# board.net
KiCad netlist of a schematic drawn in EAGLE
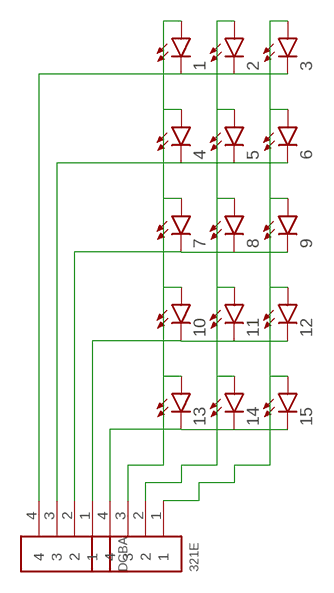
[diagram p0: schematic, sheet 1]

(export (version "E")
  (design (tool "Eeschema 10.0.6"))
  (components
    (comp (ref "1")
      (value "LED3MM")
      (footprint "eagle-import:LED3MM")
      (libsource (lib "eagle-import") (part "LED3MM"))
    )
    (comp (ref "2")
      (value "LED3MM")
      (footprint "eagle-import:LED3MM")
      (libsource (lib "eagle-import") (part "LED3MM"))
    )
    (comp (ref "3")
      (value "LED3MM")
      (footprint "eagle-import:LED3MM")
      (libsource (lib "eagle-import") (part "LED3MM"))
    )
    (comp (ref "4")
      (value "LED3MM")
      (footprint "eagle-import:LED3MM")
      (libsource (lib "eagle-import") (part "LED3MM"))
    )
    (comp (ref "5")
      (value "LED3MM")
      (footprint "eagle-import:LED3MM")
      (libsource (lib "eagle-import") (part "LED3MM"))
    )
    (comp (ref "6")
      (value "LED3MM")
      (footprint "eagle-import:LED3MM")
      (libsource (lib "eagle-import") (part "LED3MM"))
    )
    (comp (ref "7")
      (value "LED3MM")
      (footprint "eagle-import:LED3MM")
      (libsource (lib "eagle-import") (part "LED3MM"))
    )
    (comp (ref "8")
      (value "LED3MM")
      (footprint "eagle-import:LED3MM")
      (libsource (lib "eagle-import") (part "LED3MM"))
    )
    (comp (ref "9")
      (value "LED3MM")
      (footprint "eagle-import:LED3MM")
      (libsource (lib "eagle-import") (part "LED3MM"))
    )
    (comp (ref "10")
      (value "LED3MM")
      (footprint "eagle-import:LED3MM")
      (libsource (lib "eagle-import") (part "LED3MM"))
    )
    (comp (ref "11")
      (value "LED3MM")
      (footprint "eagle-import:LED3MM")
      (libsource (lib "eagle-import") (part "LED3MM"))
    )
    (comp (ref "12")
      (value "LED3MM")
      (footprint "eagle-import:LED3MM")
      (libsource (lib "eagle-import") (part "LED3MM"))
    )
    (comp (ref "13")
      (value "LED3MM")
      (footprint "eagle-import:LED3MM")
      (libsource (lib "eagle-import") (part "LED3MM"))
    )
    (comp (ref "14")
      (value "LED3MM")
      (footprint "eagle-import:LED3MM")
      (libsource (lib "eagle-import") (part "LED3MM"))
    )
    (comp (ref "15")
      (value "LED3MM")
      (footprint "eagle-import:LED3MM")
      (libsource (lib "eagle-import") (part "LED3MM"))
    )
    (comp (ref "321E")
      (value "1X4-BIG")
      (footprint "eagle-import:1X04-BIG")
      (libsource (lib "eagle-import") (part "1X4-BIG"))
    )
    (comp (ref "DCBA")
      (value "1X4-BIG")
      (footprint "eagle-import:1X04-BIG")
      (libsource (lib "eagle-import") (part "1X4-BIG"))
    )
  )
  (nets
    (net (code "1") (name "Net-(1-C)") (class "Default")
      (node (ref "1") (pin "K") (pinfunction "C_K") (pintype "passive"))
      (node (ref "2") (pin "K") (pinfunction "C_K") (pintype "passive"))
      (node (ref "3") (pin "K") (pinfunction "C_K") (pintype "passive"))
      (node (ref "DCBA") (pin "4") (pinfunction "4_4") (pintype "bidirectional"))
    )
    (net (code "2") (name "Net-(1-PadA)") (class "Default")
      (node (ref "1") (pin "A") (pinfunction "A_A") (pintype "passive"))
      (node (ref "10") (pin "A") (pinfunction "A_A") (pintype "passive"))
      (node (ref "13") (pin "A") (pinfunction "A_A") (pintype "passive"))
      (node (ref "321E") (pin "3") (pinfunction "3_3") (pintype "bidirectional"))
      (node (ref "4") (pin "A") (pinfunction "A_A") (pintype "passive"))
      (node (ref "7") (pin "A") (pinfunction "A_A") (pintype "passive"))
    )
    (net (code "3") (name "Net-(4-C)") (class "Default")
      (node (ref "4") (pin "K") (pinfunction "C_K") (pintype "passive"))
      (node (ref "5") (pin "K") (pinfunction "C_K") (pintype "passive"))
      (node (ref "6") (pin "K") (pinfunction "C_K") (pintype "passive"))
      (node (ref "DCBA") (pin "3") (pinfunction "3_3") (pintype "bidirectional"))
    )
    (net (code "4") (name "Net-(7-C)") (class "Default")
      (node (ref "7") (pin "K") (pinfunction "C_K") (pintype "passive"))
      (node (ref "8") (pin "K") (pinfunction "C_K") (pintype "passive"))
      (node (ref "9") (pin "K") (pinfunction "C_K") (pintype "passive"))
      (node (ref "DCBA") (pin "2") (pinfunction "2_2") (pintype "bidirectional"))
    )
    (net (code "5") (name "Net-(10-C)") (class "Default")
      (node (ref "10") (pin "K") (pinfunction "C_K") (pintype "passive"))
      (node (ref "11") (pin "K") (pinfunction "C_K") (pintype "passive"))
      (node (ref "12") (pin "K") (pinfunction "C_K") (pintype "passive"))
      (node (ref "DCBA") (pin "1") (pinfunction "1_1") (pintype "bidirectional"))
    )
    (net (code "6") (name "Net-(11-PadA)") (class "Default")
      (node (ref "11") (pin "A") (pinfunction "A_A") (pintype "passive"))
      (node (ref "14") (pin "A") (pinfunction "A_A") (pintype "passive"))
      (node (ref "2") (pin "A") (pinfunction "A_A") (pintype "passive"))
      (node (ref "321E") (pin "2") (pinfunction "2_2") (pintype "bidirectional"))
      (node (ref "5") (pin "A") (pinfunction "A_A") (pintype "passive"))
      (node (ref "8") (pin "A") (pinfunction "A_A") (pintype "passive"))
    )
    (net (code "7") (name "Net-(12-PadA)") (class "Default")
      (node (ref "12") (pin "A") (pinfunction "A_A") (pintype "passive"))
      (node (ref "15") (pin "A") (pinfunction "A_A") (pintype "passive"))
      (node (ref "3") (pin "A") (pinfunction "A_A") (pintype "passive"))
      (node (ref "321E") (pin "1") (pinfunction "1_1") (pintype "bidirectional"))
      (node (ref "6") (pin "A") (pinfunction "A_A") (pintype "passive"))
      (node (ref "9") (pin "A") (pinfunction "A_A") (pintype "passive"))
    )
    (net (code "8") (name "Net-(13-C)") (class "Default")
      (node (ref "13") (pin "K") (pinfunction "C_K") (pintype "passive"))
      (node (ref "14") (pin "K") (pinfunction "C_K") (pintype "passive"))
      (node (ref "15") (pin "K") (pinfunction "C_K") (pintype "passive"))
      (node (ref "321E") (pin "4") (pinfunction "4_4") (pintype "bidirectional"))
    )
  )
)
